# Side_1_v1.net
KiCad netlist of a schematic drawn in EAGLE
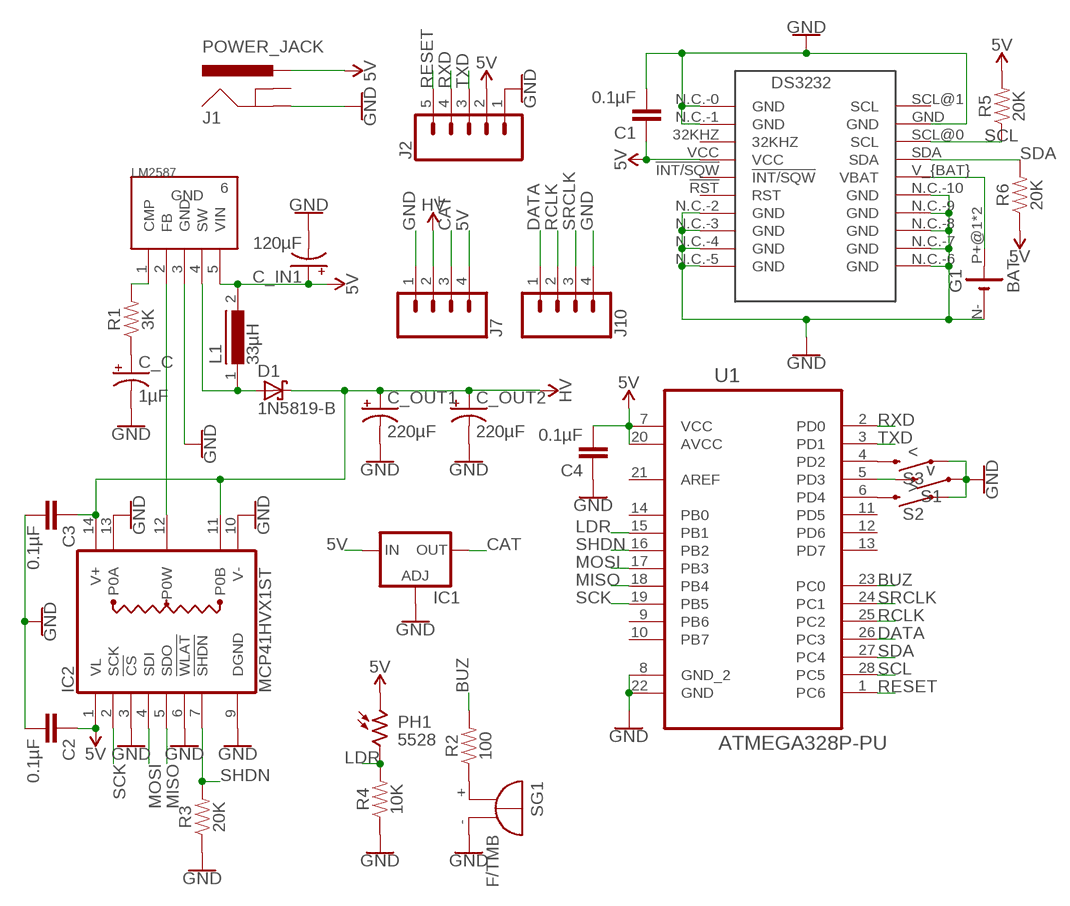
[diagram p0: schematic, sheet 1]

(export (version "E")
  (design (tool "Eeschema 10.0.6"))
  (components
    (comp (ref "C1")
      (value "0.1µF")
      (footprint "eagle-import:CAP-0.1I")
      (libsource (lib "eagle-import") (part "0.1µF-0.1''"))
    )
    (comp (ref "C2")
      (value "0.1µF")
      (footprint "eagle-import:CAP-0.1I")
      (libsource (lib "eagle-import") (part "0.1µF-0.1''"))
    )
    (comp (ref "C3")
      (value "0.1µF")
      (footprint "eagle-import:CAP-0.1I")
      (libsource (lib "eagle-import") (part "0.1µF-0.1''"))
    )
    (comp (ref "C4")
      (value "0.1µF")
      (footprint "eagle-import:CAP-0.1I")
      (libsource (lib "eagle-import") (part "0.1µF-0.1''"))
    )
    (comp (ref "C_C")
      (value "1µF")
      (footprint "eagle-import:CAP_POL_2MM")
      (libsource (lib "eagle-import") (part "CAP_POL_1µF"))
    )
    (comp (ref "C_IN1")
      (value "120µF")
      (footprint "eagle-import:CAP_POL_3MM")
      (libsource (lib "eagle-import") (part "CAP_POL_120µF"))
    )
    (comp (ref "C_OUT1")
      (value "220µF")
      (footprint "eagle-import:CPOL-RADIAL-5MM-10MM")
      (libsource (lib "eagle-import") (part "1000UF-RADIAL-5MM-25V-20%"))
    )
    (comp (ref "C_OUT2")
      (value "220µF")
      (footprint "eagle-import:CPOL-RADIAL-5MM-10MM")
      (libsource (lib "eagle-import") (part "1000UF-RADIAL-5MM-25V-20%"))
    )
    (comp (ref "D1")
      (value "1N5819-B")
      (footprint "eagle-import:DO41-7.6")
      (libsource (lib "eagle-import") (part "1N5819-B"))
    )
    (comp (ref "G1")
      (value "BAT")
      (footprint "eagle-import:CELL_RETAINER_11.6MM")
      (fields (field (name "MF") "KEYSTONE") (field (name "MPN") "2997"))
      (libsource (lib "eagle-import") (part "BATTERY-HOLDER_11.6MM"))
    )
    (comp (ref "IC1")
      (value "LM317TS")
      (footprint "eagle-import:317TS")
      (libsource (lib "eagle-import") (part "LM317TS"))
    )
    (comp (ref "IC2")
      (value "MCP41HVX1ST")
      (footprint "eagle-import:TSSOP14")
      (libsource (lib "eagle-import") (part "MCP41HVX1ST"))
    )
    (comp (ref "J1")
      (value "POWER_JACK")
      (footprint "eagle-import:POWER_JACK_PTH")
      (libsource (lib "eagle-import") (part "POWER_JACK"))
    )
    (comp (ref "J2")
      (value "CONN_05")
      (footprint "eagle-import:1X05")
      (libsource (lib "eagle-import") (part "CONN_05"))
    )
    (comp (ref "J7")
      (value "CONN_04")
      (footprint "eagle-import:1X04")
      (libsource (lib "eagle-import") (part "CONN_04"))
    )
    (comp (ref "J10")
      (value "CONN_04")
      (footprint "eagle-import:1X04")
      (libsource (lib "eagle-import") (part "CONN_04"))
    )
    (comp (ref "L1")
      (value "33µH")
      (footprint "eagle-import:MICC12")
      (libsource (lib "eagle-import") (part "MICC12"))
    )
    (comp (ref "LM2587")
      (value "LM2587S")
      (footprint "eagle-import:TO263-5")
      (libsource (lib "eagle-import") (part "LM2587S"))
    )
    (comp (ref "PH1")
      (value "5528")
      (footprint "eagle-import:5528")
      (libsource (lib "eagle-import") (part "5528"))
    )
    (comp (ref "R1")
      (value "3K")
      (footprint "eagle-import:AXIAL-0.3")
      (libsource (lib "eagle-import") (part "RESISTORAXIAL-0.3"))
    )
    (comp (ref "R2")
      (value "100")
      (footprint "eagle-import:AXIAL-0.3")
      (libsource (lib "eagle-import") (part "RESISTORAXIAL-0.3"))
    )
    (comp (ref "R3")
      (value "20K")
      (footprint "eagle-import:AXIAL-0.3")
      (libsource (lib "eagle-import") (part "RESISTORAXIAL-0.3"))
    )
    (comp (ref "R4")
      (value "10K")
      (footprint "eagle-import:AXIAL-0.3")
      (libsource (lib "eagle-import") (part "RESISTORAXIAL-0.3"))
    )
    (comp (ref "R5")
      (value "20K")
      (footprint "eagle-import:AXIAL-0.3")
      (libsource (lib "eagle-import") (part "RESISTORAXIAL-0.3"))
    )
    (comp (ref "R6")
      (value "20K")
      (footprint "eagle-import:AXIAL-0.3")
      (libsource (lib "eagle-import") (part "RESISTORAXIAL-0.3"))
    )
    (comp (ref "S1")
      (value "v")
      (footprint "eagle-import:TACTILE_SWITCH_PTH_6.0MM")
      (libsource (lib "eagle-import") (part "MOMENTARY-SWITCH-SPST-PTH-6.0MM"))
    )
    (comp (ref "S2")
      (value ">")
      (footprint "eagle-import:TACTILE_SWITCH_PTH_6.0MM")
      (libsource (lib "eagle-import") (part "MOMENTARY-SWITCH-SPST-PTH-6.0MM"))
    )
    (comp (ref "S3")
      (value "<")
      (footprint "eagle-import:TACTILE_SWITCH_PTH_6.0MM")
      (libsource (lib "eagle-import") (part "MOMENTARY-SWITCH-SPST-PTH-6.0MM"))
    )
    (comp (ref "SG1")
      (value "F/TMB")
      (footprint "eagle-import:F_TMB")
      (libsource (lib "eagle-import") (part "F/TMB"))
    )
    (comp (ref "U$1")
      (value "DS3232")
      (footprint "eagle-import:SO20-2")
      (libsource (lib "eagle-import") (part "DS3232"))
    )
    (comp (ref "U1")
      (value "ATMEGA328P-PU")
      (footprint "eagle-import:DIP254P762X457-28")
      (libsource (lib "eagle-import") (part "ATMEGA328P-PU"))
    )
  )
  (nets
    (net (code "1") (name "/BUZ") (class "Default")
      (node (ref "R2") (pin "P$2") (pinfunction "2_P$2") (pintype "passive"))
      (node (ref "U1") (pin "23") (pinfunction "PC0_23") (pintype "bidirectional"))
    )
    (net (code "2") (name "/CAT") (class "Default")
      (node (ref "IC1") (pin "2") (pinfunction "OUT_2") (pintype "passive"))
      (node (ref "J7") (pin "3") (pinfunction "3_3") (pintype "passive"))
    )
    (net (code "3") (name "/DATA") (class "Default")
      (node (ref "J10") (pin "1") (pinfunction "1_1") (pintype "passive"))
      (node (ref "U1") (pin "26") (pinfunction "PC3_26") (pintype "bidirectional"))
    )
    (net (code "4") (name "/LDR") (class "Default")
      (node (ref "PH1") (pin "2") (pinfunction "2_2") (pintype "passive"))
      (node (ref "R4") (pin "P$2") (pinfunction "2_P$2") (pintype "passive"))
      (node (ref "U1") (pin "15") (pinfunction "PB1_15") (pintype "bidirectional"))
    )
    (net (code "5") (name "/MISO") (class "Default")
      (node (ref "IC2") (pin "5") (pinfunction "SDO_5") (pintype "bidirectional"))
      (node (ref "U1") (pin "18") (pinfunction "PB4_18") (pintype "bidirectional"))
    )
    (net (code "6") (name "/MOSI") (class "Default")
      (node (ref "IC2") (pin "4") (pinfunction "SDI_4") (pintype "bidirectional"))
      (node (ref "U1") (pin "17") (pinfunction "PB3_17") (pintype "bidirectional"))
    )
    (net (code "7") (name "/RCLK") (class "Default")
      (node (ref "J10") (pin "2") (pinfunction "2_2") (pintype "passive"))
      (node (ref "U1") (pin "25") (pinfunction "PC2_25") (pintype "bidirectional"))
    )
    (net (code "8") (name "/RESET") (class "Default")
      (node (ref "J2") (pin "5") (pinfunction "5_5") (pintype "passive"))
      (node (ref "U1") (pin "1") (pinfunction "PC6_1") (pintype "bidirectional"))
    )
    (net (code "9") (name "/RXD") (class "Default")
      (node (ref "J2") (pin "4") (pinfunction "4_4") (pintype "passive"))
      (node (ref "U1") (pin "2") (pinfunction "PD0_2") (pintype "bidirectional"))
    )
    (net (code "10") (name "/SCK") (class "Default")
      (node (ref "IC2") (pin "2") (pinfunction "SCK_2") (pintype "bidirectional"))
      (node (ref "U1") (pin "19") (pinfunction "PB5_19") (pintype "bidirectional"))
    )
    (net (code "11") (name "/SCL") (class "Default")
      (node (ref "R5") (pin "P$1") (pinfunction "1_P$1") (pintype "passive"))
      (node (ref "U$1") (pin "SCL@0") (pinfunction "SCL_SCL@0") (pintype "bidirectional"))
      (node (ref "U1") (pin "28") (pinfunction "PC5_28") (pintype "bidirectional"))
    )
    (net (code "12") (name "/SDA") (class "Default")
      (node (ref "R6") (pin "P$2") (pinfunction "2_P$2") (pintype "passive"))
      (node (ref "U$1") (pin "SDA") (pinfunction "SDA_SDA") (pintype "bidirectional"))
      (node (ref "U1") (pin "27") (pinfunction "PC4_27") (pintype "bidirectional"))
    )
    (net (code "13") (name "/SHDN") (class "Default")
      (node (ref "IC2") (pin "7") (pinfunction "~{SHDN}_7") (pintype "bidirectional"))
      (node (ref "R3") (pin "P$2") (pinfunction "2_P$2") (pintype "passive"))
      (node (ref "U1") (pin "16") (pinfunction "PB2_16") (pintype "bidirectional"))
    )
    (net (code "14") (name "/SRCLK") (class "Default")
      (node (ref "J10") (pin "3") (pinfunction "3_3") (pintype "passive"))
      (node (ref "U1") (pin "24") (pinfunction "PC1_24") (pintype "bidirectional"))
    )
    (net (code "15") (name "/TXD") (class "Default")
      (node (ref "J2") (pin "3") (pinfunction "3_3") (pintype "passive"))
      (node (ref "U1") (pin "3") (pinfunction "PD1_3") (pintype "bidirectional"))
    )
    (net (code "16") (name "5V") (class "Default")
      (node (ref "C1") (pin "1") (pinfunction "1_1") (pintype "passive"))
      (node (ref "C2") (pin "1") (pinfunction "1_1") (pintype "passive"))
      (node (ref "C4") (pin "2") (pinfunction "2_2") (pintype "passive"))
      (node (ref "C_IN1") (pin "POS") (pinfunction "+_POS") (pintype "passive"))
      (node (ref "IC1") (pin "3") (pinfunction "IN_3") (pintype "input"))
      (node (ref "IC2") (pin "1") (pinfunction "VL_1") (pintype "power_in"))
      (node (ref "J1") (pin "PWR") (pinfunction "PWR_PWR") (pintype "bidirectional"))
      (node (ref "J2") (pin "2") (pinfunction "2_2") (pintype "passive"))
      (node (ref "J7") (pin "4") (pinfunction "4_4") (pintype "passive"))
      (node (ref "L1") (pin "2") (pinfunction "2_2") (pintype "passive"))
      (node (ref "LM2587") (pin "5") (pinfunction "VIN_5") (pintype "bidirectional"))
      (node (ref "PH1") (pin "1") (pinfunction "1_1") (pintype "passive"))
      (node (ref "R5") (pin "P$2") (pinfunction "2_P$2") (pintype "passive"))
      (node (ref "R6") (pin "P$1") (pinfunction "1_P$1") (pintype "passive"))
      (node (ref "U$1") (pin "VCC") (pinfunction "VCC_VCC") (pintype "bidirectional"))
      (node (ref "U1") (pin "20") (pinfunction "AVCC_20") (pintype "power_in"))
      (node (ref "U1") (pin "7") (pinfunction "VCC_7") (pintype "power_in"))
    )
    (net (code "17") (name "GND") (class "Default")
      (node (ref "C1") (pin "2") (pinfunction "2_2") (pintype "passive"))
      (node (ref "C2") (pin "2") (pinfunction "2_2") (pintype "passive"))
      (node (ref "C3") (pin "2") (pinfunction "2_2") (pintype "passive"))
      (node (ref "C4") (pin "1") (pinfunction "1_1") (pintype "passive"))
      (node (ref "C_C") (pin "NEG") (pinfunction "-_NEG") (pintype "passive"))
      (node (ref "C_IN1") (pin "NEG") (pinfunction "-_NEG") (pintype "passive"))
      (node (ref "C_OUT1") (pin "-") (pinfunction "-_-") (pintype "passive"))
      (node (ref "C_OUT2") (pin "-") (pinfunction "-_-") (pintype "passive"))
      (node (ref "G1") (pin "N-") (pinfunction "-_N-") (pintype "passive"))
      (node (ref "IC1") (pin "1") (pinfunction "ADJ_1") (pintype "input"))
      (node (ref "IC2") (pin "10") (pinfunction "V-_10") (pintype "power_in"))
      (node (ref "IC2") (pin "13") (pinfunction "P0A_13") (pintype "passive"))
      (node (ref "IC2") (pin "3") (pinfunction "~{CS}_3") (pintype "bidirectional"))
      (node (ref "IC2") (pin "6") (pinfunction "~{WLAT}_6") (pintype "bidirectional"))
      (node (ref "IC2") (pin "9") (pinfunction "DGND_9") (pintype "power_in"))
      (node (ref "J1") (pin "GND") (pinfunction "GND_GND") (pintype "bidirectional"))
      (node (ref "J10") (pin "4") (pinfunction "4_4") (pintype "passive"))
      (node (ref "J2") (pin "1") (pinfunction "1_1") (pintype "passive"))
      (node (ref "J7") (pin "1") (pinfunction "1_1") (pintype "passive"))
      (node (ref "LM2587") (pin "3") (pinfunction "GND_3") (pintype "bidirectional"))
      (node (ref "R3") (pin "P$1") (pinfunction "1_P$1") (pintype "passive"))
      (node (ref "R4") (pin "P$1") (pinfunction "1_P$1") (pintype "passive"))
      (node (ref "S1") (pin "1") (pinfunction "1_1") (pintype "passive"))
      (node (ref "S2") (pin "1") (pinfunction "1_1") (pintype "passive"))
      (node (ref "S3") (pin "1") (pinfunction "1_1") (pintype "passive"))
      (node (ref "SG1") (pin "-") (pinfunction "-_-") (pintype "passive"))
      (node (ref "U$1") (pin "GND") (pinfunction "GND_GND") (pintype "bidirectional"))
      (node (ref "U$1") (pin "N.C.-0") (pinfunction "GND_N.C.-0") (pintype "bidirectional"))
      (node (ref "U$1") (pin "N.C.-1") (pinfunction "GND_N.C.-1") (pintype "bidirectional"))
      (node (ref "U$1") (pin "N.C.-10") (pinfunction "GND_N.C.-10") (pintype "bidirectional"))
      (node (ref "U$1") (pin "N.C.-2") (pinfunction "GND_N.C.-2") (pintype "bidirectional"))
      (node (ref "U$1") (pin "N.C.-3") (pinfunction "GND_N.C.-3") (pintype "bidirectional"))
      (node (ref "U$1") (pin "N.C.-4") (pinfunction "GND_N.C.-4") (pintype "bidirectional"))
      (node (ref "U$1") (pin "N.C.-5") (pinfunction "GND_N.C.-5") (pintype "bidirectional"))
      (node (ref "U$1") (pin "N.C.-6") (pinfunction "GND_N.C.-6") (pintype "bidirectional"))
      (node (ref "U$1") (pin "N.C.-7") (pinfunction "GND_N.C.-7") (pintype "bidirectional"))
      (node (ref "U$1") (pin "N.C.-8") (pinfunction "GND_N.C.-8") (pintype "bidirectional"))
      (node (ref "U$1") (pin "N.C.-9") (pinfunction "GND_N.C.-9") (pintype "bidirectional"))
      (node (ref "U1") (pin "22") (pinfunction "GND_22") (pintype "passive"))
      (node (ref "U1") (pin "8") (pinfunction "GND_2_8") (pintype "passive"))
    )
    (net (code "18") (name "HV") (class "Default")
      (node (ref "C3") (pin "1") (pinfunction "1_1") (pintype "passive"))
      (node (ref "C_OUT1") (pin "+") (pinfunction "+_+") (pintype "passive"))
      (node (ref "C_OUT2") (pin "+") (pinfunction "+_+") (pintype "passive"))
      (node (ref "D1") (pin "C") (pinfunction "C_C") (pintype "passive"))
      (node (ref "IC2") (pin "11") (pinfunction "P0B_11") (pintype "passive"))
      (node (ref "IC2") (pin "14") (pinfunction "V+_14") (pintype "power_in"))
      (node (ref "J7") (pin "2") (pinfunction "2_2") (pintype "passive"))
    )
    (net (code "19") (name "Net-(C_C-+)") (class "Default")
      (node (ref "C_C") (pin "POS") (pinfunction "+_POS") (pintype "passive"))
      (node (ref "R1") (pin "P$1") (pinfunction "1_P$1") (pintype "passive"))
    )
    (net (code "20") (name "Net-(IC2-P0W)") (class "Default")
      (node (ref "IC2") (pin "12") (pinfunction "P0W_12") (pintype "passive"))
      (node (ref "LM2587") (pin "2") (pinfunction "FB_2") (pintype "bidirectional"))
    )
    (net (code "21") (name "Net-(LM2587-CMP)") (class "Default")
      (node (ref "LM2587") (pin "1") (pinfunction "CMP_1") (pintype "bidirectional"))
      (node (ref "R1") (pin "P$2") (pinfunction "2_P$2") (pintype "passive"))
    )
    (net (code "22") (name "Net-(LM2587-SW)") (class "Default")
      (node (ref "D1") (pin "A") (pinfunction "A_A") (pintype "passive"))
      (node (ref "L1") (pin "1") (pinfunction "1_1") (pintype "passive"))
      (node (ref "LM2587") (pin "4") (pinfunction "SW_4") (pintype "bidirectional"))
    )
    (net (code "23") (name "Net-(R2-1)") (class "Default")
      (node (ref "R2") (pin "P$1") (pinfunction "1_P$1") (pintype "passive"))
      (node (ref "SG1") (pin "+") (pinfunction "+_+") (pintype "passive"))
    )
    (net (code "24") (name "Net-(S1-2)") (class "Default")
      (node (ref "S1") (pin "3") (pinfunction "2_3") (pintype "passive"))
      (node (ref "U1") (pin "5") (pinfunction "PD3_5") (pintype "bidirectional"))
    )
    (net (code "25") (name "Net-(S2-2)") (class "Default")
      (node (ref "S2") (pin "3") (pinfunction "2_3") (pintype "passive"))
      (node (ref "U1") (pin "6") (pinfunction "PD4_6") (pintype "bidirectional"))
    )
    (net (code "26") (name "Net-(S3-2)") (class "Default")
      (node (ref "S3") (pin "3") (pinfunction "2_3") (pintype "passive"))
      (node (ref "U1") (pin "4") (pinfunction "PD2_4") (pintype "bidirectional"))
    )
    (net (code "27") (name "Net-(U$1-VBAT)") (class "Default")
      (node (ref "G1") (pin "P+@1") (pinfunction "+_P+@1") (pintype "passive"))
      (node (ref "G1") (pin "P+@2") (pinfunction "+_P+@2") (pintype "passive"))
      (node (ref "U$1") (pin "V_{BAT}") (pinfunction "VBAT_V_{BAT}") (pintype "bidirectional"))
    )
    (net (code "28") (name "unconnected-(J1-PadGNDBREAK)") (class "Default")
      (node (ref "J1") (pin "GNDBREAK") (pinfunction "GNDBREAK_GNDBREAK") (pintype "bidirectional"))
    )
    (net (code "29") (name "unconnected-(LM2587-GND-Pad6)") (class "Default")
      (node (ref "LM2587") (pin "6") (pinfunction "GND_6") (pintype "bidirectional"))
    )
    (net (code "30") (name "unconnected-(U$1-Pad32KHZ)") (class "Default")
      (node (ref "U$1") (pin "32KHZ") (pinfunction "32KHZ_32KHZ") (pintype "bidirectional"))
    )
    (net (code "31") (name "unconnected-(U$1-RST-Pad!RST)") (class "Default")
      (node (ref "U$1") (pin "!RST") (pinfunction "RST_!RST") (pintype "bidirectional"))
    )
    (net (code "32") (name "unconnected-(U$1-SCL-PadSCL@1)") (class "Default")
      (node (ref "U$1") (pin "SCL@1") (pinfunction "SCL_SCL@1") (pintype "bidirectional"))
    )
    (net (code "33") (name "unconnected-(U$1-~{INT{slash}SQW}-Pad!INT{slash}SQW)") (class "Default")
      (node (ref "U$1") (pin "!INT/SQW") (pinfunction "~{INT/SQW}_!INT/SQW") (pintype "bidirectional"))
    )
    (net (code "34") (name "unconnected-(U1-AREF-Pad21)") (class "Default")
      (node (ref "U1") (pin "21") (pinfunction "AREF_21") (pintype "input"))
    )
    (net (code "35") (name "unconnected-(U1-PB0-Pad14)") (class "Default")
      (node (ref "U1") (pin "14") (pinfunction "PB0_14") (pintype "bidirectional"))
    )
    (net (code "36") (name "unconnected-(U1-PB6-Pad9)") (class "Default")
      (node (ref "U1") (pin "9") (pinfunction "PB6_9") (pintype "bidirectional"))
    )
    (net (code "37") (name "unconnected-(U1-PB7-Pad10)") (class "Default")
      (node (ref "U1") (pin "10") (pinfunction "PB7_10") (pintype "bidirectional"))
    )
    (net (code "38") (name "unconnected-(U1-PD5-Pad11)") (class "Default")
      (node (ref "U1") (pin "11") (pinfunction "PD5_11") (pintype "bidirectional"))
    )
    (net (code "39") (name "unconnected-(U1-PD6-Pad12)") (class "Default")
      (node (ref "U1") (pin "12") (pinfunction "PD6_12") (pintype "bidirectional"))
    )
    (net (code "40") (name "unconnected-(U1-PD7-Pad13)") (class "Default")
      (node (ref "U1") (pin "13") (pinfunction "PD7_13") (pintype "bidirectional"))
    )
  )
)
